# MegaSound9x_HaGeHa_SIP_v1.net
KiCad netlist of a schematic drawn in EAGLE
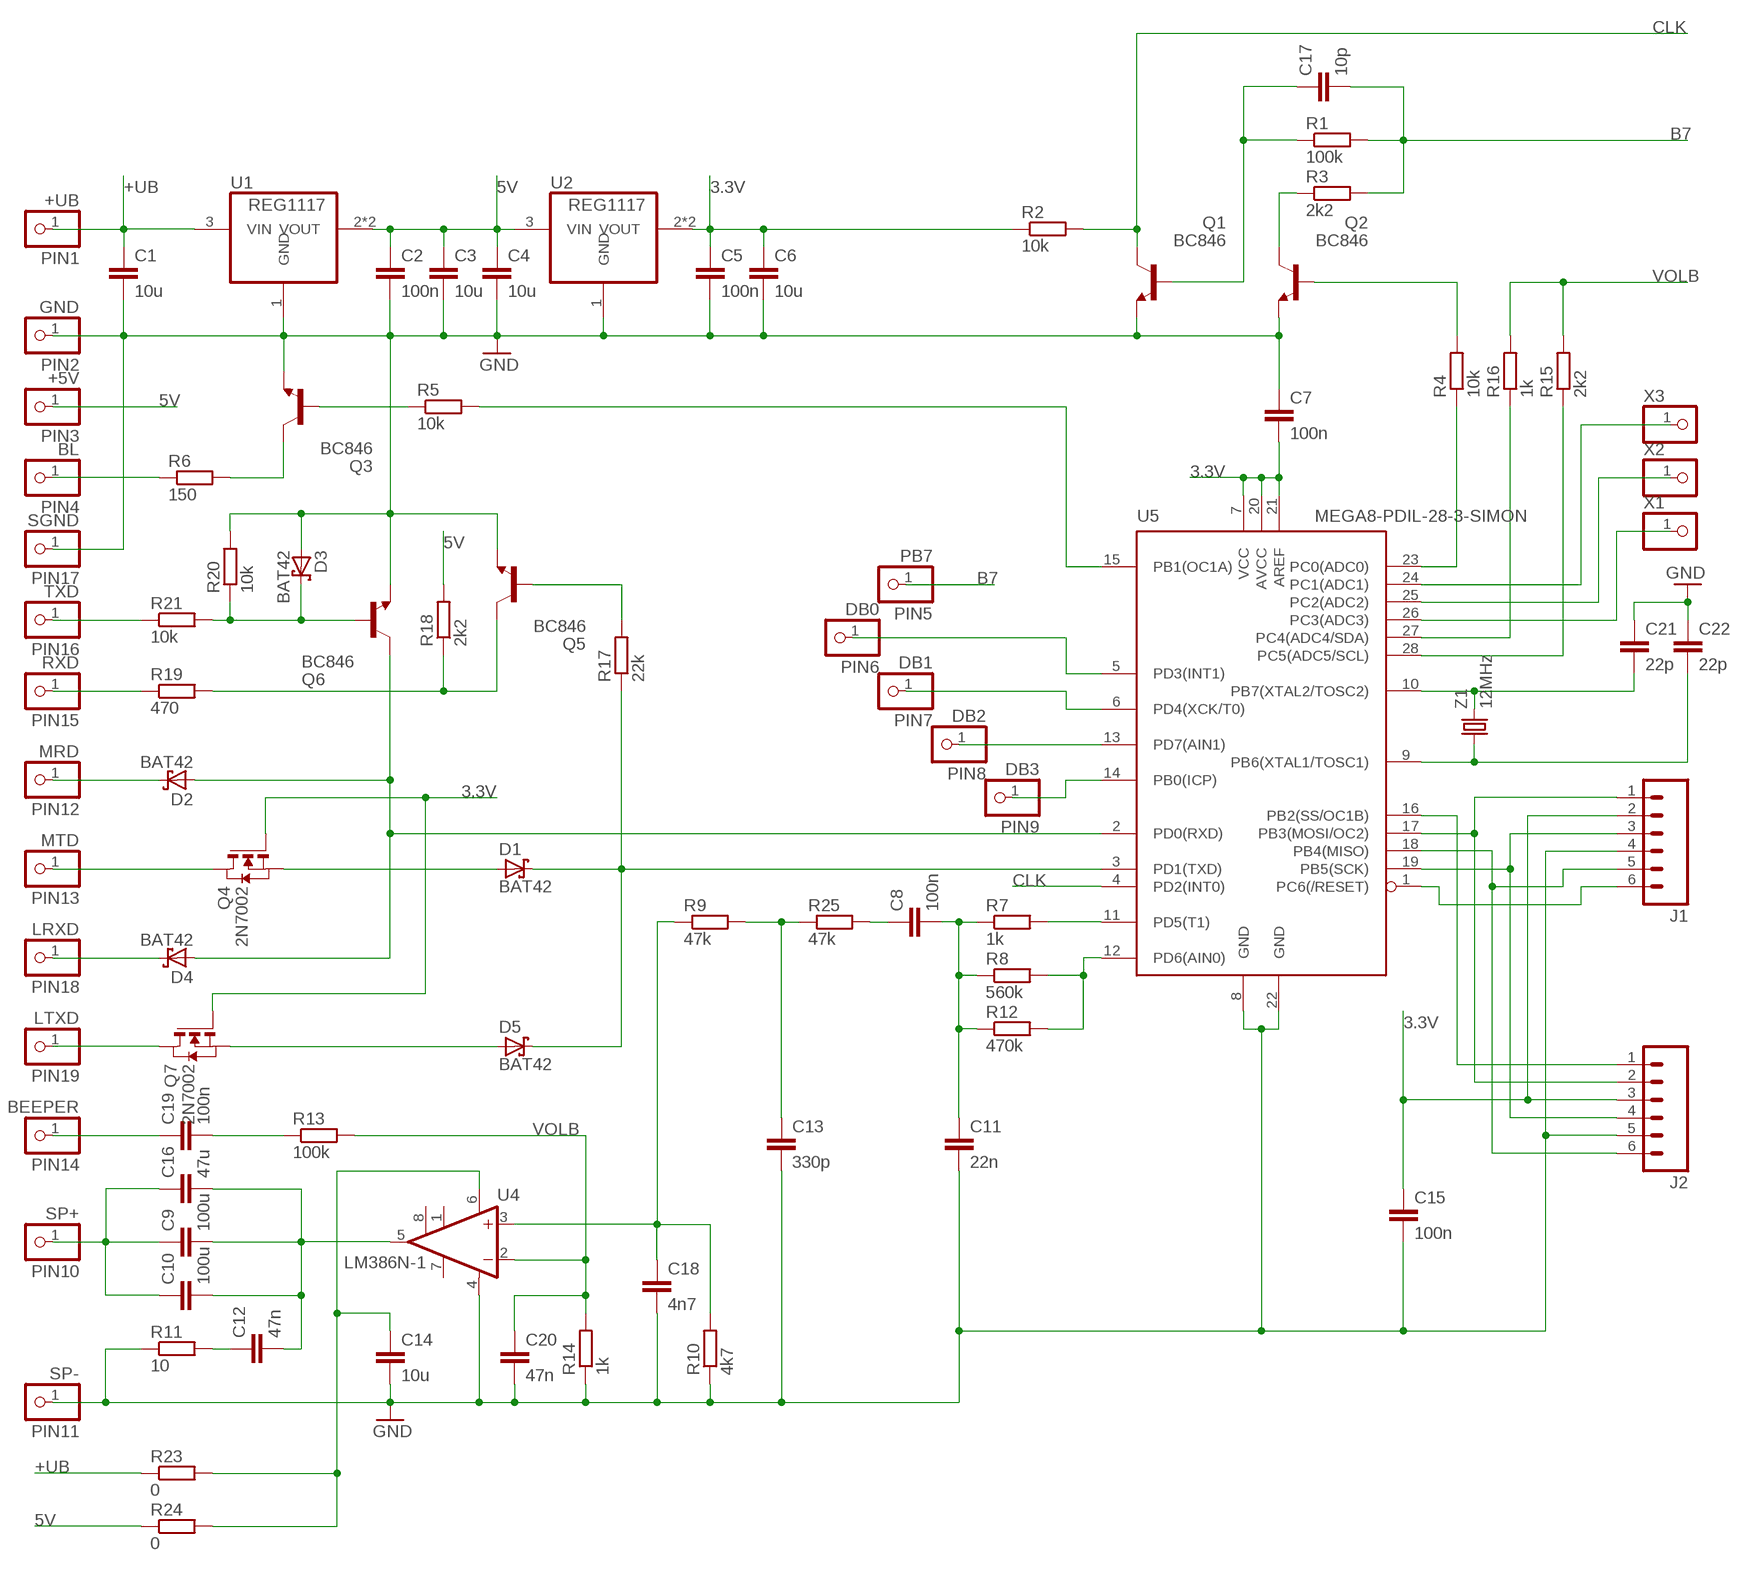
[diagram p0: schematic, sheet 1]

(export (version "E")
  (design (tool "Eeschema 10.0.6"))
  (components
    (comp (ref "+5V")
      (value "PIN3")
      (footprint "eagle-import:1X01")
      (libsource (lib "eagle-import") (part "PINHD-1X1"))
    )
    (comp (ref "+UB")
      (value "PIN1")
      (footprint "eagle-import:1X01")
      (libsource (lib "eagle-import") (part "PINHD-1X1"))
    )
    (comp (ref "BEEPER")
      (value "PIN14")
      (footprint "eagle-import:1X01")
      (libsource (lib "eagle-import") (part "PINHD-1X1"))
    )
    (comp (ref "BL")
      (value "PIN4")
      (footprint "eagle-import:1X01")
      (libsource (lib "eagle-import") (part "PINHD-1X1"))
    )
    (comp (ref "C1")
      (value "10u")
      (footprint "eagle-import:C1206")
      (libsource (lib "eagle-import") (part "C-EUC1206"))
    )
    (comp (ref "C2")
      (value "100n")
      (footprint "eagle-import:C1206")
      (libsource (lib "eagle-import") (part "C-EUC1206"))
    )
    (comp (ref "C3")
      (value "10u")
      (footprint "eagle-import:C1206")
      (libsource (lib "eagle-import") (part "C-EUC1206"))
    )
    (comp (ref "C4")
      (value "10u")
      (footprint "eagle-import:C1206")
      (libsource (lib "eagle-import") (part "C-EUC1206"))
    )
    (comp (ref "C5")
      (value "100n")
      (footprint "eagle-import:C1206")
      (libsource (lib "eagle-import") (part "C-EUC1206"))
    )
    (comp (ref "C6")
      (value "10u")
      (footprint "eagle-import:C1206")
      (libsource (lib "eagle-import") (part "C-EUC1206"))
    )
    (comp (ref "C7")
      (value "100n")
      (footprint "eagle-import:C1206")
      (libsource (lib "eagle-import") (part "C-EUC1206"))
    )
    (comp (ref "C8")
      (value "100n")
      (footprint "eagle-import:C1206")
      (libsource (lib "eagle-import") (part "C-EUC1206"))
    )
    (comp (ref "C9")
      (value "100u")
      (footprint "eagle-import:C1206")
      (libsource (lib "eagle-import") (part "C-EUC1206"))
    )
    (comp (ref "C10")
      (value "100u")
      (footprint "eagle-import:C1206")
      (libsource (lib "eagle-import") (part "C-EUC1206"))
    )
    (comp (ref "C11")
      (value "22n")
      (footprint "eagle-import:C1206")
      (libsource (lib "eagle-import") (part "C-EUC1206"))
    )
    (comp (ref "C12")
      (value "47n")
      (footprint "eagle-import:C1206")
      (libsource (lib "eagle-import") (part "C-EUC1206"))
    )
    (comp (ref "C13")
      (value "330p")
      (footprint "eagle-import:C1206")
      (libsource (lib "eagle-import") (part "C-EUC1206"))
    )
    (comp (ref "C14")
      (value "10u")
      (footprint "eagle-import:C1206")
      (libsource (lib "eagle-import") (part "C-EUC1206"))
    )
    (comp (ref "C15")
      (value "100n")
      (footprint "eagle-import:C1206")
      (libsource (lib "eagle-import") (part "C-EUC1206"))
    )
    (comp (ref "C16")
      (value "47u")
      (footprint "eagle-import:C1206")
      (libsource (lib "eagle-import") (part "C-EUC1206"))
    )
    (comp (ref "C17")
      (value "10p")
      (footprint "eagle-import:C1206")
      (libsource (lib "eagle-import") (part "C-EUC1206"))
    )
    (comp (ref "C18")
      (value "4n7")
      (footprint "eagle-import:C1206")
      (libsource (lib "eagle-import") (part "C-EUC1206"))
    )
    (comp (ref "C19")
      (value "100n")
      (footprint "eagle-import:C1206")
      (libsource (lib "eagle-import") (part "C-EUC1206"))
    )
    (comp (ref "C20")
      (value "47n")
      (footprint "eagle-import:C1206")
      (libsource (lib "eagle-import") (part "C-EUC1206"))
    )
    (comp (ref "C21")
      (value "22p")
      (footprint "eagle-import:C1206")
      (libsource (lib "eagle-import") (part "C-EUC1206"))
    )
    (comp (ref "C22")
      (value "22p")
      (footprint "eagle-import:C1206")
      (libsource (lib "eagle-import") (part "C-EUC1206"))
    )
    (comp (ref "D1")
      (value "BAT42")
      (footprint "eagle-import:SOD123")
      (libsource (lib "eagle-import") (part "BAT42"))
    )
    (comp (ref "D2")
      (value "BAT42")
      (footprint "eagle-import:SOD123")
      (libsource (lib "eagle-import") (part "BAT42"))
    )
    (comp (ref "D3")
      (value "BAT42")
      (footprint "eagle-import:SOD123")
      (libsource (lib "eagle-import") (part "BAT42"))
    )
    (comp (ref "D4")
      (value "BAT42")
      (footprint "eagle-import:SOD123")
      (libsource (lib "eagle-import") (part "BAT42"))
    )
    (comp (ref "D5")
      (value "BAT42")
      (footprint "eagle-import:SOD123")
      (libsource (lib "eagle-import") (part "BAT42"))
    )
    (comp (ref "DB0")
      (value "PIN6")
      (footprint "eagle-import:1X01")
      (libsource (lib "eagle-import") (part "PINHD-1X1"))
    )
    (comp (ref "DB1")
      (value "PIN7")
      (footprint "eagle-import:1X01")
      (libsource (lib "eagle-import") (part "PINHD-1X1"))
    )
    (comp (ref "DB2")
      (value "PIN8")
      (footprint "eagle-import:1X01")
      (libsource (lib "eagle-import") (part "PINHD-1X1"))
    )
    (comp (ref "DB3")
      (value "PIN9")
      (footprint "eagle-import:1X01")
      (libsource (lib "eagle-import") (part "PINHD-1X1"))
    )
    (comp (ref "GND")
      (value "PIN2")
      (footprint "eagle-import:1X01")
      (libsource (lib "eagle-import") (part "PINHD-1X1"))
    )
    (comp (ref "J1")
      (value "M06SIP")
      (footprint "eagle-import:1X06")
      (libsource (lib "eagle-import") (part "M06SIP"))
    )
    (comp (ref "J2")
      (value "M06SIP")
      (footprint "eagle-import:1X06")
      (libsource (lib "eagle-import") (part "M06SIP"))
    )
    (comp (ref "LRXD")
      (value "PIN18")
      (footprint "eagle-import:1X01")
      (libsource (lib "eagle-import") (part "PINHD-1X1"))
    )
    (comp (ref "LTXD")
      (value "PIN19")
      (footprint "eagle-import:1X01")
      (libsource (lib "eagle-import") (part "PINHD-1X1"))
    )
    (comp (ref "MRD")
      (value "PIN12")
      (footprint "eagle-import:1X01")
      (libsource (lib "eagle-import") (part "PINHD-1X1"))
    )
    (comp (ref "MTD")
      (value "PIN13")
      (footprint "eagle-import:1X01")
      (libsource (lib "eagle-import") (part "PINHD-1X1"))
    )
    (comp (ref "PB7")
      (value "PIN5")
      (footprint "eagle-import:1X01")
      (libsource (lib "eagle-import") (part "PINHD-1X1"))
    )
    (comp (ref "Q1")
      (value "BC846")
      (footprint "eagle-import:SOT23")
      (libsource (lib "eagle-import") (part "BC846"))
    )
    (comp (ref "Q2")
      (value "BC846")
      (footprint "eagle-import:SOT23")
      (libsource (lib "eagle-import") (part "BC846"))
    )
    (comp (ref "Q3")
      (value "BC846")
      (footprint "eagle-import:SOT23")
      (libsource (lib "eagle-import") (part "BC846"))
    )
    (comp (ref "Q4")
      (value "2N7002")
      (footprint "eagle-import:SOT-23")
      (libsource (lib "eagle-import") (part "NMOSSOT23"))
    )
    (comp (ref "Q5")
      (value "BC846")
      (footprint "eagle-import:SOT23")
      (libsource (lib "eagle-import") (part "BC846"))
    )
    (comp (ref "Q6")
      (value "BC846")
      (footprint "eagle-import:SOT23")
      (libsource (lib "eagle-import") (part "BC846"))
    )
    (comp (ref "Q7")
      (value "2N7002")
      (footprint "eagle-import:SOT-23")
      (libsource (lib "eagle-import") (part "NMOSSOT23"))
    )
    (comp (ref "R1")
      (value "100k")
      (footprint "eagle-import:R1206")
      (libsource (lib "eagle-import") (part "R-EU_R1206"))
    )
    (comp (ref "R2")
      (value "10k")
      (footprint "eagle-import:R1206")
      (libsource (lib "eagle-import") (part "R-EU_R1206"))
    )
    (comp (ref "R3")
      (value "2k2")
      (footprint "eagle-import:R1206")
      (libsource (lib "eagle-import") (part "R-EU_R1206"))
    )
    (comp (ref "R4")
      (value "10k")
      (footprint "eagle-import:R1206")
      (libsource (lib "eagle-import") (part "R-EU_R1206"))
    )
    (comp (ref "R5")
      (value "10k")
      (footprint "eagle-import:R1206")
      (libsource (lib "eagle-import") (part "R-EU_R1206"))
    )
    (comp (ref "R6")
      (value "150")
      (footprint "eagle-import:R1206")
      (libsource (lib "eagle-import") (part "R-EU_R1206"))
    )
    (comp (ref "R7")
      (value "1k")
      (footprint "eagle-import:R1206")
      (libsource (lib "eagle-import") (part "R-EU_R1206"))
    )
    (comp (ref "R8")
      (value "560k")
      (footprint "eagle-import:R1206")
      (libsource (lib "eagle-import") (part "R-EU_R1206"))
    )
    (comp (ref "R9")
      (value "47k")
      (footprint "eagle-import:R1206")
      (libsource (lib "eagle-import") (part "R-EU_R1206"))
    )
    (comp (ref "R10")
      (value "4k7")
      (footprint "eagle-import:R1206")
      (libsource (lib "eagle-import") (part "R-EU_R1206"))
    )
    (comp (ref "R11")
      (value "10")
      (footprint "eagle-import:R1206")
      (libsource (lib "eagle-import") (part "R-EU_R1206"))
    )
    (comp (ref "R12")
      (value "470k")
      (footprint "eagle-import:R1206")
      (libsource (lib "eagle-import") (part "R-EU_R1206"))
    )
    (comp (ref "R13")
      (value "100k")
      (footprint "eagle-import:R1206")
      (libsource (lib "eagle-import") (part "R-EU_R1206"))
    )
    (comp (ref "R14")
      (value "1k")
      (footprint "eagle-import:R1206")
      (libsource (lib "eagle-import") (part "R-EU_R1206"))
    )
    (comp (ref "R15")
      (value "2k2")
      (footprint "eagle-import:R1206")
      (libsource (lib "eagle-import") (part "R-EU_R1206"))
    )
    (comp (ref "R16")
      (value "1k")
      (footprint "eagle-import:R1206")
      (libsource (lib "eagle-import") (part "R-EU_R1206"))
    )
    (comp (ref "R17")
      (value "22k")
      (footprint "eagle-import:R1206")
      (libsource (lib "eagle-import") (part "R-EU_R1206"))
    )
    (comp (ref "R18")
      (value "2k2")
      (footprint "eagle-import:R1206")
      (libsource (lib "eagle-import") (part "R-EU_R1206"))
    )
    (comp (ref "R19")
      (value "470")
      (footprint "eagle-import:R1206")
      (libsource (lib "eagle-import") (part "R-EU_R1206"))
    )
    (comp (ref "R20")
      (value "10k")
      (footprint "eagle-import:R1206")
      (libsource (lib "eagle-import") (part "R-EU_R1206"))
    )
    (comp (ref "R21")
      (value "10k")
      (footprint "eagle-import:R1206")
      (libsource (lib "eagle-import") (part "R-EU_R1206"))
    )
    (comp (ref "R23")
      (value "0")
      (footprint "eagle-import:R1206")
      (libsource (lib "eagle-import") (part "R-EU_R1206"))
    )
    (comp (ref "R24")
      (value "0")
      (footprint "eagle-import:R1206")
      (libsource (lib "eagle-import") (part "R-EU_R1206"))
    )
    (comp (ref "R25")
      (value "47k")
      (footprint "eagle-import:R1206")
      (libsource (lib "eagle-import") (part "R-EU_R1206"))
    )
    (comp (ref "RXD")
      (value "PIN15")
      (footprint "eagle-import:1X01")
      (libsource (lib "eagle-import") (part "PINHD-1X1"))
    )
    (comp (ref "SGND")
      (value "PIN17")
      (footprint "eagle-import:1X01")
      (libsource (lib "eagle-import") (part "PINHD-1X1"))
    )
    (comp (ref "SP+")
      (value "PIN10")
      (footprint "eagle-import:1X01")
      (libsource (lib "eagle-import") (part "PINHD-1X1"))
    )
    (comp (ref "SP-")
      (value "PIN11")
      (footprint "eagle-import:1X01")
      (libsource (lib "eagle-import") (part "PINHD-1X1"))
    )
    (comp (ref "TXD")
      (value "PIN16")
      (footprint "eagle-import:1X01")
      (libsource (lib "eagle-import") (part "PINHD-1X1"))
    )
    (comp (ref "U1")
      (value "REG1117")
      (footprint "eagle-import:SOT223")
      (libsource (lib "eagle-import") (part "REG1117"))
    )
    (comp (ref "U2")
      (value "REG1117")
      (footprint "eagle-import:SOT223")
      (fields
        (field (name "MPN") "REG1117")
        (field (name "OC_FARNELL") "1097566")
        (field (name "OC_NEWARK") "14P6981")
      )
      (libsource (lib "eagle-import") (part "REG1117"))
    )
    (comp (ref "U4")
      (value "LM386N-1")
      (footprint "eagle-import:DIL08")
      (libsource (lib "eagle-import") (part "LM386?-N1"))
    )
    (comp (ref "U5")
      (value "MEGA8-PDIL-28-3-SIMON")
      (footprint "eagle-import:DIL28-3-SIMON")
      (libsource (lib "eagle-import") (part "MEGA8-PDIL-28-3-SIMON"))
    )
    (comp (ref "X1")
      (value "PINHD-1X1")
      (footprint "eagle-import:1X01")
      (libsource (lib "eagle-import") (part "PINHD-1X1"))
    )
    (comp (ref "X2")
      (value "PINHD-1X1")
      (footprint "eagle-import:1X01")
      (libsource (lib "eagle-import") (part "PINHD-1X1"))
    )
    (comp (ref "X3")
      (value "PINHD-1X1")
      (footprint "eagle-import:1X01")
      (libsource (lib "eagle-import") (part "PINHD-1X1"))
    )
    (comp (ref "Z1")
      (value "12MHz")
      (footprint "eagle-import:HC49US")
      (libsource (lib "eagle-import") (part "CRYSTALHC49US"))
    )
  )
  (nets
    (net (code "1") (name "/+UB") (class "Default")
      (node (ref "+UB") (pin "1") (pinfunction "1_1") (pintype "passive"))
      (node (ref "C1") (pin "1") (pinfunction "1_1") (pintype "passive"))
      (node (ref "R23") (pin "1") (pinfunction "1_1") (pintype "passive"))
      (node (ref "U1") (pin "3") (pinfunction "VIN_3") (pintype "input"))
    )
    (net (code "2") (name "/3.3V") (class "Default")
      (node (ref "C15") (pin "1") (pinfunction "1_1") (pintype "passive"))
      (node (ref "C5") (pin "1") (pinfunction "1_1") (pintype "passive"))
      (node (ref "C6") (pin "1") (pinfunction "1_1") (pintype "passive"))
      (node (ref "C7") (pin "2") (pinfunction "2_2") (pintype "passive"))
      (node (ref "J1") (pin "2") (pinfunction "2_2") (pintype "passive"))
      (node (ref "J2") (pin "3") (pinfunction "3_3") (pintype "passive"))
      (node (ref "Q4") (pin "3") (pinfunction "G_3") (pintype "passive"))
      (node (ref "Q7") (pin "3") (pinfunction "G_3") (pintype "passive"))
      (node (ref "R2") (pin "1") (pinfunction "1_1") (pintype "passive"))
      (node (ref "U2") (pin "2") (pinfunction "VOUT_2") (pintype "output"))
      (node (ref "U2") (pin "4") (pinfunction "VOUT_4") (pintype "output"))
      (node (ref "U5") (pin "20") (pinfunction "AVCC_20") (pintype "power_in"))
      (node (ref "U5") (pin "21") (pinfunction "AREF_21") (pintype "passive"))
      (node (ref "U5") (pin "7") (pinfunction "VCC_7") (pintype "power_in"))
    )
    (net (code "3") (name "/5V") (class "Default")
      (node (ref "+5V") (pin "1") (pinfunction "1_1") (pintype "passive"))
      (node (ref "C2") (pin "1") (pinfunction "1_1") (pintype "passive"))
      (node (ref "C3") (pin "1") (pinfunction "1_1") (pintype "passive"))
      (node (ref "C4") (pin "1") (pinfunction "1_1") (pintype "passive"))
      (node (ref "R18") (pin "2") (pinfunction "2_2") (pintype "passive"))
      (node (ref "R24") (pin "1") (pinfunction "1_1") (pintype "passive"))
      (node (ref "U1") (pin "2") (pinfunction "VOUT_2") (pintype "output"))
      (node (ref "U1") (pin "4") (pinfunction "VOUT_4") (pintype "output"))
      (node (ref "U2") (pin "3") (pinfunction "VIN_3") (pintype "input"))
    )
    (net (code "4") (name "/B7") (class "Default")
      (node (ref "C17") (pin "2") (pinfunction "2_2") (pintype "passive"))
      (node (ref "PB7") (pin "1") (pinfunction "1_1") (pintype "passive"))
      (node (ref "R1") (pin "2") (pinfunction "2_2") (pintype "passive"))
      (node (ref "R3") (pin "2") (pinfunction "2_2") (pintype "passive"))
    )
    (net (code "5") (name "/CLK") (class "Default")
      (node (ref "Q1") (pin "3") (pinfunction "C_3") (pintype "passive"))
      (node (ref "R2") (pin "2") (pinfunction "2_2") (pintype "passive"))
      (node (ref "U5") (pin "4") (pinfunction "PD2(INT0)_4") (pintype "bidirectional"))
    )
    (net (code "6") (name "/VOLB") (class "Default")
      (node (ref "C20") (pin "1") (pinfunction "1_1") (pintype "passive"))
      (node (ref "R13") (pin "2") (pinfunction "2_2") (pintype "passive"))
      (node (ref "R14") (pin "2") (pinfunction "2_2") (pintype "passive"))
      (node (ref "R15") (pin "2") (pinfunction "2_2") (pintype "passive"))
      (node (ref "R16") (pin "2") (pinfunction "2_2") (pintype "passive"))
      (node (ref "U4") (pin "2") (pinfunction "-IN_2") (pintype "input"))
    )
    (net (code "7") (name "GND") (class "Default")
      (node (ref "C1") (pin "2") (pinfunction "2_2") (pintype "passive"))
      (node (ref "C11") (pin "2") (pinfunction "2_2") (pintype "passive"))
      (node (ref "C13") (pin "2") (pinfunction "2_2") (pintype "passive"))
      (node (ref "C14") (pin "2") (pinfunction "2_2") (pintype "passive"))
      (node (ref "C15") (pin "2") (pinfunction "2_2") (pintype "passive"))
      (node (ref "C18") (pin "2") (pinfunction "2_2") (pintype "passive"))
      (node (ref "C2") (pin "2") (pinfunction "2_2") (pintype "passive"))
      (node (ref "C20") (pin "2") (pinfunction "2_2") (pintype "passive"))
      (node (ref "C21") (pin "1") (pinfunction "1_1") (pintype "passive"))
      (node (ref "C22") (pin "1") (pinfunction "1_1") (pintype "passive"))
      (node (ref "C3") (pin "2") (pinfunction "2_2") (pintype "passive"))
      (node (ref "C4") (pin "2") (pinfunction "2_2") (pintype "passive"))
      (node (ref "C5") (pin "2") (pinfunction "2_2") (pintype "passive"))
      (node (ref "C6") (pin "2") (pinfunction "2_2") (pintype "passive"))
      (node (ref "C7") (pin "1") (pinfunction "1_1") (pintype "passive"))
      (node (ref "D3") (pin "A") (pinfunction "A_A") (pintype "passive"))
      (node (ref "GND") (pin "1") (pinfunction "1_1") (pintype "passive"))
      (node (ref "J1") (pin "4") (pinfunction "4_4") (pintype "passive"))
      (node (ref "J2") (pin "5") (pinfunction "5_5") (pintype "passive"))
      (node (ref "Q1") (pin "2") (pinfunction "E_2") (pintype "passive"))
      (node (ref "Q2") (pin "2") (pinfunction "E_2") (pintype "passive"))
      (node (ref "Q3") (pin "2") (pinfunction "E_2") (pintype "passive"))
      (node (ref "Q5") (pin "2") (pinfunction "E_2") (pintype "passive"))
      (node (ref "Q6") (pin "2") (pinfunction "E_2") (pintype "passive"))
      (node (ref "R10") (pin "1") (pinfunction "1_1") (pintype "passive"))
      (node (ref "R11") (pin "1") (pinfunction "1_1") (pintype "passive"))
      (node (ref "R14") (pin "1") (pinfunction "1_1") (pintype "passive"))
      (node (ref "R20") (pin "2") (pinfunction "2_2") (pintype "passive"))
      (node (ref "SGND") (pin "1") (pinfunction "1_1") (pintype "passive"))
      (node (ref "SP-") (pin "1") (pinfunction "1_1") (pintype "passive"))
      (node (ref "U1") (pin "1") (pinfunction "GND_1") (pintype "power_in"))
      (node (ref "U2") (pin "1") (pinfunction "GND_1") (pintype "power_in"))
      (node (ref "U4") (pin "4") (pinfunction "GND_4") (pintype "power_in"))
      (node (ref "U5") (pin "22") (pinfunction "GND_22") (pintype "power_in"))
      (node (ref "U5") (pin "8") (pinfunction "GND_8") (pintype "power_in"))
    )
    (net (code "8") (name "Net-(BEEPER-Pad1)") (class "Default")
      (node (ref "BEEPER") (pin "1") (pinfunction "1_1") (pintype "passive"))
      (node (ref "C19") (pin "1") (pinfunction "1_1") (pintype "passive"))
    )
    (net (code "9") (name "Net-(BL-Pad1)") (class "Default")
      (node (ref "BL") (pin "1") (pinfunction "1_1") (pintype "passive"))
      (node (ref "R6") (pin "1") (pinfunction "1_1") (pintype "passive"))
    )
    (net (code "10") (name "Net-(C8-Pad1)") (class "Default")
      (node (ref "C8") (pin "1") (pinfunction "1_1") (pintype "passive"))
      (node (ref "R25") (pin "2") (pinfunction "2_2") (pintype "passive"))
    )
    (net (code "11") (name "Net-(C10-Pad1)") (class "Default")
      (node (ref "C10") (pin "1") (pinfunction "1_1") (pintype "passive"))
      (node (ref "C16") (pin "1") (pinfunction "1_1") (pintype "passive"))
      (node (ref "C9") (pin "1") (pinfunction "1_1") (pintype "passive"))
      (node (ref "SP+") (pin "1") (pinfunction "1_1") (pintype "passive"))
    )
    (net (code "12") (name "Net-(C11-Pad1)") (class "Default")
      (node (ref "C11") (pin "1") (pinfunction "1_1") (pintype "passive"))
      (node (ref "C8") (pin "2") (pinfunction "2_2") (pintype "passive"))
      (node (ref "R12") (pin "1") (pinfunction "1_1") (pintype "passive"))
      (node (ref "R7") (pin "1") (pinfunction "1_1") (pintype "passive"))
      (node (ref "R8") (pin "1") (pinfunction "1_1") (pintype "passive"))
    )
    (net (code "13") (name "Net-(C12-Pad1)") (class "Default")
      (node (ref "C12") (pin "1") (pinfunction "1_1") (pintype "passive"))
      (node (ref "R11") (pin "2") (pinfunction "2_2") (pintype "passive"))
    )
    (net (code "14") (name "Net-(C13-Pad1)") (class "Default")
      (node (ref "C13") (pin "1") (pinfunction "1_1") (pintype "passive"))
      (node (ref "R25") (pin "1") (pinfunction "1_1") (pintype "passive"))
      (node (ref "R9") (pin "2") (pinfunction "2_2") (pintype "passive"))
    )
    (net (code "15") (name "Net-(C19-Pad2)") (class "Default")
      (node (ref "C19") (pin "2") (pinfunction "2_2") (pintype "passive"))
      (node (ref "R13") (pin "1") (pinfunction "1_1") (pintype "passive"))
    )
    (net (code "16") (name "Net-(D2-PadC)") (class "Default")
      (node (ref "D2") (pin "C") (pinfunction "C_C") (pintype "passive"))
      (node (ref "MRD") (pin "1") (pinfunction "1_1") (pintype "passive"))
    )
    (net (code "17") (name "Net-(D4-PadC)") (class "Default")
      (node (ref "D4") (pin "C") (pinfunction "C_C") (pintype "passive"))
      (node (ref "LRXD") (pin "1") (pinfunction "1_1") (pintype "passive"))
    )
    (net (code "18") (name "Net-(Q1-B)") (class "Default")
      (node (ref "C17") (pin "1") (pinfunction "1_1") (pintype "passive"))
      (node (ref "Q1") (pin "1") (pinfunction "B_1") (pintype "passive"))
      (node (ref "R1") (pin "1") (pinfunction "1_1") (pintype "passive"))
    )
    (net (code "19") (name "Net-(Q2-B)") (class "Default")
      (node (ref "Q2") (pin "1") (pinfunction "B_1") (pintype "passive"))
      (node (ref "R4") (pin "2") (pinfunction "2_2") (pintype "passive"))
    )
    (net (code "20") (name "Net-(Q2-C)") (class "Default")
      (node (ref "Q2") (pin "3") (pinfunction "C_3") (pintype "passive"))
      (node (ref "R3") (pin "1") (pinfunction "1_1") (pintype "passive"))
    )
    (net (code "21") (name "Net-(Q3-B)") (class "Default")
      (node (ref "Q3") (pin "1") (pinfunction "B_1") (pintype "passive"))
      (node (ref "R5") (pin "1") (pinfunction "1_1") (pintype "passive"))
    )
    (net (code "22") (name "Net-(Q3-C)") (class "Default")
      (node (ref "Q3") (pin "3") (pinfunction "C_3") (pintype "passive"))
      (node (ref "R6") (pin "2") (pinfunction "2_2") (pintype "passive"))
    )
    (net (code "23") (name "Net-(Q4-D)") (class "Default")
      (node (ref "MTD") (pin "1") (pinfunction "1_1") (pintype "passive"))
      (node (ref "Q4") (pin "1") (pinfunction "D_1") (pintype "passive"))
    )
    (net (code "24") (name "Net-(Q4-S)") (class "Default")
      (node (ref "D1") (pin "A") (pinfunction "A_A") (pintype "passive"))
      (node (ref "Q4") (pin "2") (pinfunction "S_2") (pintype "passive"))
    )
    (net (code "25") (name "Net-(Q5-B)") (class "Default")
      (node (ref "Q5") (pin "1") (pinfunction "B_1") (pintype "passive"))
      (node (ref "R17") (pin "2") (pinfunction "2_2") (pintype "passive"))
    )
    (net (code "26") (name "Net-(Q5-C)") (class "Default")
      (node (ref "Q5") (pin "3") (pinfunction "C_3") (pintype "passive"))
      (node (ref "R18") (pin "1") (pinfunction "1_1") (pintype "passive"))
      (node (ref "R19") (pin "2") (pinfunction "2_2") (pintype "passive"))
    )
    (net (code "27") (name "Net-(Q6-B)") (class "Default")
      (node (ref "D3") (pin "C") (pinfunction "C_C") (pintype "passive"))
      (node (ref "Q6") (pin "1") (pinfunction "B_1") (pintype "passive"))
      (node (ref "R20") (pin "1") (pinfunction "1_1") (pintype "passive"))
      (node (ref "R21") (pin "2") (pinfunction "2_2") (pintype "passive"))
    )
    (net (code "28") (name "Net-(Q6-C)") (class "Default")
      (node (ref "D2") (pin "A") (pinfunction "A_A") (pintype "passive"))
      (node (ref "D4") (pin "A") (pinfunction "A_A") (pintype "passive"))
      (node (ref "Q6") (pin "3") (pinfunction "C_3") (pintype "passive"))
      (node (ref "U5") (pin "2") (pinfunction "PD0(RXD)_2") (pintype "bidirectional"))
    )
    (net (code "29") (name "Net-(Q7-D)") (class "Default")
      (node (ref "LTXD") (pin "1") (pinfunction "1_1") (pintype "passive"))
      (node (ref "Q7") (pin "1") (pinfunction "D_1") (pintype "passive"))
    )
    (net (code "30") (name "Net-(Q7-S)") (class "Default")
      (node (ref "D5") (pin "A") (pinfunction "A_A") (pintype "passive"))
      (node (ref "Q7") (pin "2") (pinfunction "S_2") (pintype "passive"))
    )
    (net (code "31") (name "Net-(R19-Pad1)") (class "Default")
      (node (ref "R19") (pin "1") (pinfunction "1_1") (pintype "passive"))
      (node (ref "RXD") (pin "1") (pinfunction "1_1") (pintype "passive"))
    )
    (net (code "32") (name "Net-(R21-Pad1)") (class "Default")
      (node (ref "R21") (pin "1") (pinfunction "1_1") (pintype "passive"))
      (node (ref "TXD") (pin "1") (pinfunction "1_1") (pintype "passive"))
    )
    (net (code "33") (name "Net-(U4-+IN)") (class "Default")
      (node (ref "C18") (pin "1") (pinfunction "1_1") (pintype "passive"))
      (node (ref "R10") (pin "2") (pinfunction "2_2") (pintype "passive"))
      (node (ref "R9") (pin "1") (pinfunction "1_1") (pintype "passive"))
      (node (ref "U4") (pin "3") (pinfunction "+IN_3") (pintype "input"))
    )
    (net (code "34") (name "Net-(U4-OUT)") (class "Default")
      (node (ref "C10") (pin "2") (pinfunction "2_2") (pintype "passive"))
      (node (ref "C12") (pin "2") (pinfunction "2_2") (pintype "passive"))
      (node (ref "C16") (pin "2") (pinfunction "2_2") (pintype "passive"))
      (node (ref "C9") (pin "2") (pinfunction "2_2") (pintype "passive"))
      (node (ref "U4") (pin "5") (pinfunction "OUT_5") (pintype "output"))
    )
    (net (code "35") (name "Net-(U4-VS)") (class "Default")
      (node (ref "C14") (pin "1") (pinfunction "1_1") (pintype "passive"))
      (node (ref "R23") (pin "2") (pinfunction "2_2") (pintype "passive"))
      (node (ref "R24") (pin "2") (pinfunction "2_2") (pintype "passive"))
      (node (ref "U4") (pin "6") (pinfunction "VS_6") (pintype "power_in"))
    )
    (net (code "36") (name "Net-(U5-PB0(ICP))") (class "Default")
      (node (ref "DB3") (pin "1") (pinfunction "1_1") (pintype "passive"))
      (node (ref "U5") (pin "14") (pinfunction "PB0(ICP)_14") (pintype "bidirectional"))
    )
    (net (code "37") (name "Net-(U5-PB1(OC1A))") (class "Default")
      (node (ref "R5") (pin "2") (pinfunction "2_2") (pintype "passive"))
      (node (ref "U5") (pin "15") (pinfunction "PB1(OC1A)_15") (pintype "bidirectional"))
    )
    (net (code "38") (name "Net-(U5-PB2(SS{slash}OC1B))") (class "Default")
      (node (ref "J2") (pin "1") (pinfunction "1_1") (pintype "passive"))
      (node (ref "U5") (pin "16") (pinfunction "PB2(SS/OC1B)_16") (pintype "bidirectional"))
    )
    (net (code "39") (name "Net-(U5-PB3(MOSI{slash}OC2))") (class "Default")
      (node (ref "J1") (pin "1") (pinfunction "1_1") (pintype "passive"))
      (node (ref "J2") (pin "2") (pinfunction "2_2") (pintype "passive"))
      (node (ref "U5") (pin "17") (pinfunction "PB3(MOSI/OC2)_17") (pintype "bidirectional"))
    )
    (net (code "40") (name "Net-(U5-PB4(MISO))") (class "Default")
      (node (ref "J1") (pin "5") (pinfunction "5_5") (pintype "passive"))
      (node (ref "J2") (pin "6") (pinfunction "6_6") (pintype "passive"))
      (node (ref "U5") (pin "18") (pinfunction "PB4(MISO)_18") (pintype "bidirectional"))
    )
    (net (code "41") (name "Net-(U5-PB5(SCK))") (class "Default")
      (node (ref "J1") (pin "3") (pinfunction "3_3") (pintype "passive"))
      (node (ref "J2") (pin "4") (pinfunction "4_4") (pintype "passive"))
      (node (ref "U5") (pin "19") (pinfunction "PB5(SCK)_19") (pintype "bidirectional"))
    )
    (net (code "42") (name "Net-(U5-PB6(XTAL1{slash}TOSC1))") (class "Default")
      (node (ref "C22") (pin "2") (pinfunction "2_2") (pintype "passive"))
      (node (ref "U5") (pin "9") (pinfunction "PB6(XTAL1/TOSC1)_9") (pintype "bidirectional"))
      (node (ref "Z1") (pin "1") (pinfunction "1_1") (pintype "passive"))
    )
    (net (code "43") (name "Net-(U5-PB7(XTAL2{slash}TOSC2))") (class "Default")
      (node (ref "C21") (pin "2") (pinfunction "2_2") (pintype "passive"))
      (node (ref "U5") (pin "10") (pinfunction "PB7(XTAL2/TOSC2)_10") (pintype "bidirectional"))
      (node (ref "Z1") (pin "2") (pinfunction "2_2") (pintype "passive"))
    )
    (net (code "44") (name "Net-(U5-PC0(ADC0))") (class "Default")
      (node (ref "R4") (pin "1") (pinfunction "1_1") (pintype "passive"))
      (node (ref "U5") (pin "23") (pinfunction "PC0(ADC0)_23") (pintype "bidirectional"))
    )
    (net (code "45") (name "Net-(U5-PC1(ADC1))") (class "Default")
      (node (ref "U5") (pin "24") (pinfunction "PC1(ADC1)_24") (pintype "bidirectional"))
      (node (ref "X3") (pin "1") (pinfunction "1_1") (pintype "passive"))
    )
    (net (code "46") (name "Net-(U5-PC2(ADC2))") (class "Default")
      (node (ref "U5") (pin "25") (pinfunction "PC2(ADC2)_25") (pintype "bidirectional"))
      (node (ref "X2") (pin "1") (pinfunction "1_1") (pintype "passive"))
    )
    (net (code "47") (name "Net-(U5-PC3(ADC3))") (class "Default")
      (node (ref "U5") (pin "26") (pinfunction "PC3(ADC3)_26") (pintype "bidirectional"))
      (node (ref "X1") (pin "1") (pinfunction "1_1") (pintype "passive"))
    )
    (net (code "48") (name "Net-(U5-PC4(ADC4{slash}SDA))") (class "Default")
      (node (ref "R16") (pin "1") (pinfunction "1_1") (pintype "passive"))
      (node (ref "U5") (pin "27") (pinfunction "PC4(ADC4/SDA)_27") (pintype "bidirectional"))
    )
    (net (code "49") (name "Net-(U5-PC5(ADC5{slash}SCL))") (class "Default")
      (node (ref "R15") (pin "1") (pinfunction "1_1") (pintype "passive"))
      (node (ref "U5") (pin "28") (pinfunction "PC5(ADC5/SCL)_28") (pintype "bidirectional"))
    )
    (net (code "50") (name "Net-(U5-PC6({slash}RESET))") (class "Default")
      (node (ref "J1") (pin "6") (pinfunction "6_6") (pintype "passive"))
      (node (ref "U5") (pin "1") (pinfunction "PC6(/RESET)_1") (pintype "bidirectional"))
    )
    (net (code "51") (name "Net-(U5-PD1(TXD))") (class "Default")
      (node (ref "D1") (pin "C") (pinfunction "C_C") (pintype "passive"))
      (node (ref "D5") (pin "C") (pinfunction "C_C") (pintype "passive"))
      (node (ref "R17") (pin "1") (pinfunction "1_1") (pintype "passive"))
      (node (ref "U5") (pin "3") (pinfunction "PD1(TXD)_3") (pintype "bidirectional"))
    )
    (net (code "52") (name "Net-(U5-PD3(INT1))") (class "Default")
      (node (ref "DB0") (pin "1") (pinfunction "1_1") (pintype "passive"))
      (node (ref "U5") (pin "5") (pinfunction "PD3(INT1)_5") (pintype "bidirectional"))
    )
    (net (code "53") (name "Net-(U5-PD4(XCK{slash}T0))") (class "Default")
      (node (ref "DB1") (pin "1") (pinfunction "1_1") (pintype "passive"))
      (node (ref "U5") (pin "6") (pinfunction "PD4(XCK/T0)_6") (pintype "bidirectional"))
    )
    (net (code "54") (name "Net-(U5-PD5(T1))") (class "Default")
      (node (ref "R7") (pin "2") (pinfunction "2_2") (pintype "passive"))
      (node (ref "U5") (pin "11") (pinfunction "PD5(T1)_11") (pintype "bidirectional"))
    )
    (net (code "55") (name "Net-(U5-PD6(AIN0))") (class "Default")
      (node (ref "R12") (pin "2") (pinfunction "2_2") (pintype "passive"))
      (node (ref "R8") (pin "2") (pinfunction "2_2") (pintype "passive"))
      (node (ref "U5") (pin "12") (pinfunction "PD6(AIN0)_12") (pintype "bidirectional"))
    )
    (net (code "56") (name "Net-(U5-PD7(AIN1))") (class "Default")
      (node (ref "DB2") (pin "1") (pinfunction "1_1") (pintype "passive"))
      (node (ref "U5") (pin "13") (pinfunction "PD7(AIN1)_13") (pintype "bidirectional"))
    )
    (net (code "57") (name "unconnected-(U4-BYPASS-Pad7)") (class "Default")
      (node (ref "U4") (pin "7") (pinfunction "BYPASS_7") (pintype "passive"))
    )
    (net (code "58") (name "unconnected-(U4-GAIN-Pad1)") (class "Default")
      (node (ref "U4") (pin "1") (pinfunction "GAIN_1") (pintype "passive"))
    )
    (net (code "59") (name "unconnected-(U4-GAIN-Pad8)") (class "Default")
      (node (ref "U4") (pin "8") (pinfunction "GAIN_8") (pintype "passive"))
    )
  )
)
